# Kube_LoRaWAN_Module.net
KiCad netlist of a schematic drawn in EAGLE
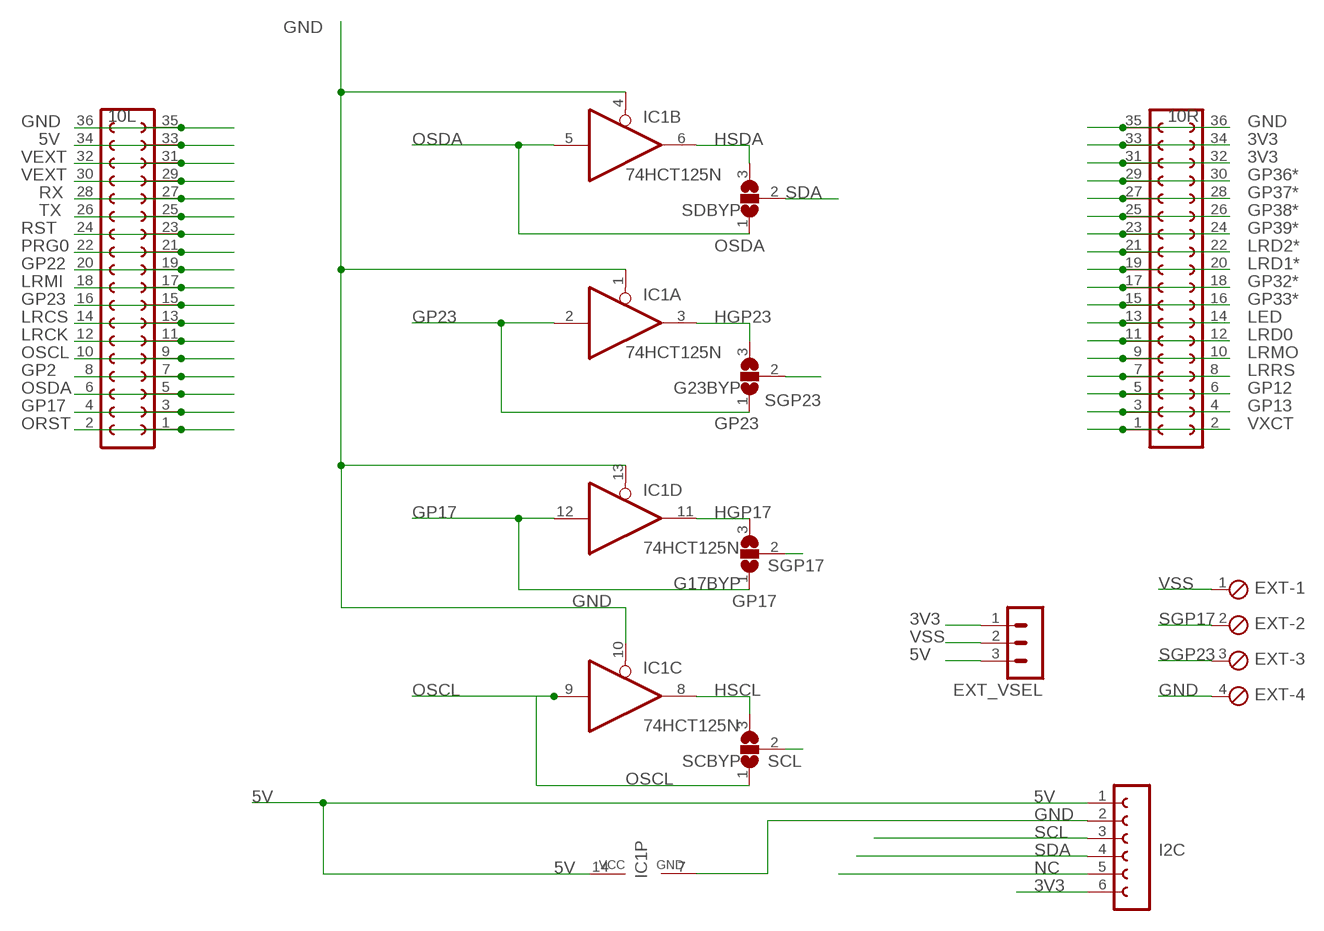
[diagram p0: schematic, sheet 1]

(export (version "E")
  (design (tool "Eeschema 10.0.6"))
  (components
    (comp (ref "10L")
      (value "15")
      (footprint "eagle-import:FE18-2")
      (libsource (lib "eagle-import") (part "FE18-2"))
    )
    (comp (ref "10R")
      (value "15")
      (footprint "eagle-import:FE18-2")
      (libsource (lib "eagle-import") (part "FE18-2"))
    )
    (comp (ref "EXT")
      (value "MPT4")
      (footprint "eagle-import:4POL254")
      (libsource (lib "eagle-import") (part "MPT4"))
    )
    (comp (ref "EXT_VSEL")
      (value "MA03-1")
      (footprint "eagle-import:MA03-1")
      (libsource (lib "eagle-import") (part "MA03-1"))
    )
    (comp (ref "G17BYP")
      (value "SJ2W")
      (footprint "eagle-import:SJ_2")
      (libsource (lib "eagle-import") (part "SJ2W"))
    )
    (comp (ref "G23BYP")
      (value "SJ2W")
      (footprint "eagle-import:SJ_2")
      (libsource (lib "eagle-import") (part "SJ2W"))
    )
    (comp (ref "I2C")
      (value "FE06-1")
      (footprint "eagle-import:FE06")
      (libsource (lib "eagle-import") (part "FE06-1"))
    )
    (comp (ref "IC1")
      (value "74HCT125N")
      (footprint "eagle-import:DIL14")
      (libsource (lib "eagle-import") (part "74125NHCT"))
    )
    (comp (ref "SCBYP")
      (value "SJ2W")
      (footprint "eagle-import:SJ_2")
      (libsource (lib "eagle-import") (part "SJ2W"))
    )
    (comp (ref "SDBYP")
      (value "SJ2W")
      (footprint "eagle-import:SJ_2")
      (libsource (lib "eagle-import") (part "SJ2W"))
    )
  )
  (nets
    (net (code "1") (name "/3V3") (class "Default")
      (node (ref "10R") (pin "31") (pinfunction "31_31") (pintype "passive"))
      (node (ref "10R") (pin "32") (pinfunction "32_32") (pintype "passive"))
      (node (ref "10R") (pin "33") (pinfunction "33_33") (pintype "passive"))
      (node (ref "10R") (pin "34") (pinfunction "34_34") (pintype "passive"))
      (node (ref "EXT_VSEL") (pin "1") (pinfunction "1_1") (pintype "passive"))
      (node (ref "I2C") (pin "6") (pinfunction "6_6") (pintype "passive"))
    )
    (net (code "2") (name "/5V") (class "Default")
      (node (ref "10L") (pin "33") (pinfunction "33_33") (pintype "passive"))
      (node (ref "10L") (pin "34") (pinfunction "34_34") (pintype "passive"))
      (node (ref "EXT_VSEL") (pin "3") (pinfunction "3_3") (pintype "passive"))
      (node (ref "I2C") (pin "1") (pinfunction "1_1") (pintype "passive"))
      (node (ref "IC1") (pin "14") (pinfunction "VCC_14") (pintype "power_in"))
    )
    (net (code "3") (name "/GND") (class "Default")
      (node (ref "10L") (pin "35") (pinfunction "35_35") (pintype "passive"))
      (node (ref "10L") (pin "36") (pinfunction "36_36") (pintype "passive"))
      (node (ref "10R") (pin "35") (pinfunction "35_35") (pintype "passive"))
      (node (ref "10R") (pin "36") (pinfunction "36_36") (pintype "passive"))
      (node (ref "EXT") (pin "4") (pinfunction "1_4") (pintype "passive"))
      (node (ref "I2C") (pin "2") (pinfunction "2_2") (pintype "passive"))
      (node (ref "IC1") (pin "1") (pinfunction "OE_1") (pintype "input"))
      (node (ref "IC1") (pin "10") (pinfunction "OE_10") (pintype "input"))
      (node (ref "IC1") (pin "13") (pinfunction "OE_13") (pintype "input"))
      (node (ref "IC1") (pin "4") (pinfunction "OE_4") (pintype "input"))
      (node (ref "IC1") (pin "7") (pinfunction "GND_7") (pintype "power_in"))
    )
    (net (code "4") (name "/GP2") (class "Default")
      (node (ref "10L") (pin "7") (pinfunction "7_7") (pintype "passive"))
      (node (ref "10L") (pin "8") (pinfunction "8_8") (pintype "passive"))
    )
    (net (code "5") (name "/GP12") (class "Default")
      (node (ref "10R") (pin "5") (pinfunction "5_5") (pintype "passive"))
      (node (ref "10R") (pin "6") (pinfunction "6_6") (pintype "passive"))
    )
    (net (code "6") (name "/GP13") (class "Default")
      (node (ref "10R") (pin "3") (pinfunction "3_3") (pintype "passive"))
      (node (ref "10R") (pin "4") (pinfunction "4_4") (pintype "passive"))
    )
    (net (code "7") (name "/GP17") (class "Default")
      (node (ref "10L") (pin "3") (pinfunction "3_3") (pintype "passive"))
      (node (ref "10L") (pin "4") (pinfunction "4_4") (pintype "passive"))
      (node (ref "G17BYP") (pin "1") (pinfunction "1_1") (pintype "passive"))
      (node (ref "IC1") (pin "12") (pinfunction "I_12") (pintype "input"))
    )
    (net (code "8") (name "/GP22") (class "Default")
      (node (ref "10L") (pin "19") (pinfunction "19_19") (pintype "passive"))
      (node (ref "10L") (pin "20") (pinfunction "20_20") (pintype "passive"))
    )
    (net (code "9") (name "/GP23") (class "Default")
      (node (ref "10L") (pin "15") (pinfunction "15_15") (pintype "passive"))
      (node (ref "10L") (pin "16") (pinfunction "16_16") (pintype "passive"))
      (node (ref "G23BYP") (pin "1") (pinfunction "1_1") (pintype "passive"))
      (node (ref "IC1") (pin "2") (pinfunction "I_2") (pintype "input"))
    )
    (net (code "10") (name "/GP32*") (class "Default")
      (node (ref "10R") (pin "17") (pinfunction "17_17") (pintype "passive"))
      (node (ref "10R") (pin "18") (pinfunction "18_18") (pintype "passive"))
    )
    (net (code "11") (name "/GP33*") (class "Default")
      (node (ref "10R") (pin "15") (pinfunction "15_15") (pintype "passive"))
      (node (ref "10R") (pin "16") (pinfunction "16_16") (pintype "passive"))
    )
    (net (code "12") (name "/GP36*") (class "Default")
      (node (ref "10R") (pin "29") (pinfunction "29_29") (pintype "passive"))
      (node (ref "10R") (pin "30") (pinfunction "30_30") (pintype "passive"))
    )
    (net (code "13") (name "/GP37*") (class "Default")
      (node (ref "10R") (pin "27") (pinfunction "27_27") (pintype "passive"))
      (node (ref "10R") (pin "28") (pinfunction "28_28") (pintype "passive"))
    )
    (net (code "14") (name "/GP38*") (class "Default")
      (node (ref "10R") (pin "25") (pinfunction "25_25") (pintype "passive"))
      (node (ref "10R") (pin "26") (pinfunction "26_26") (pintype "passive"))
    )
    (net (code "15") (name "/GP39*") (class "Default")
      (node (ref "10R") (pin "23") (pinfunction "23_23") (pintype "passive"))
      (node (ref "10R") (pin "24") (pinfunction "24_24") (pintype "passive"))
    )
    (net (code "16") (name "/HGP17") (class "Default")
      (node (ref "G17BYP") (pin "3") (pinfunction "3_3") (pintype "passive"))
      (node (ref "IC1") (pin "11") (pinfunction "O_11") (pintype "tri_state"))
    )
    (net (code "17") (name "/HGP23") (class "Default")
      (node (ref "G23BYP") (pin "3") (pinfunction "3_3") (pintype "passive"))
      (node (ref "IC1") (pin "3") (pinfunction "O_3") (pintype "tri_state"))
    )
    (net (code "18") (name "/HSCL") (class "Default")
      (node (ref "IC1") (pin "8") (pinfunction "O_8") (pintype "tri_state"))
      (node (ref "SCBYP") (pin "3") (pinfunction "3_3") (pintype "passive"))
    )
    (net (code "19") (name "/HSDA") (class "Default")
      (node (ref "IC1") (pin "6") (pinfunction "O_6") (pintype "tri_state"))
      (node (ref "SDBYP") (pin "3") (pinfunction "3_3") (pintype "passive"))
    )
    (net (code "20") (name "/LED") (class "Default")
      (node (ref "10R") (pin "13") (pinfunction "13_13") (pintype "passive"))
      (node (ref "10R") (pin "14") (pinfunction "14_14") (pintype "passive"))
    )
    (net (code "21") (name "/LRCK") (class "Default")
      (node (ref "10L") (pin "11") (pinfunction "11_11") (pintype "passive"))
      (node (ref "10L") (pin "12") (pinfunction "12_12") (pintype "passive"))
    )
    (net (code "22") (name "/LRCS") (class "Default")
      (node (ref "10L") (pin "13") (pinfunction "13_13") (pintype "passive"))
      (node (ref "10L") (pin "14") (pinfunction "14_14") (pintype "passive"))
    )
    (net (code "23") (name "/LRD0") (class "Default")
      (node (ref "10R") (pin "11") (pinfunction "11_11") (pintype "passive"))
      (node (ref "10R") (pin "12") (pinfunction "12_12") (pintype "passive"))
    )
    (net (code "24") (name "/LRD1*") (class "Default")
      (node (ref "10R") (pin "19") (pinfunction "19_19") (pintype "passive"))
      (node (ref "10R") (pin "20") (pinfunction "20_20") (pintype "passive"))
    )
    (net (code "25") (name "/LRD2*") (class "Default")
      (node (ref "10R") (pin "21") (pinfunction "21_21") (pintype "passive"))
      (node (ref "10R") (pin "22") (pinfunction "22_22") (pintype "passive"))
    )
    (net (code "26") (name "/LRMI") (class "Default")
      (node (ref "10L") (pin "17") (pinfunction "17_17") (pintype "passive"))
      (node (ref "10L") (pin "18") (pinfunction "18_18") (pintype "passive"))
    )
    (net (code "27") (name "/LRMO") (class "Default")
      (node (ref "10R") (pin "10") (pinfunction "10_10") (pintype "passive"))
      (node (ref "10R") (pin "9") (pinfunction "9_9") (pintype "passive"))
    )
    (net (code "28") (name "/LRRS") (class "Default")
      (node (ref "10R") (pin "7") (pinfunction "7_7") (pintype "passive"))
      (node (ref "10R") (pin "8") (pinfunction "8_8") (pintype "passive"))
    )
    (net (code "29") (name "/NC") (class "Default")
      (node (ref "I2C") (pin "5") (pinfunction "5_5") (pintype "passive"))
    )
    (net (code "30") (name "/ORST") (class "Default")
      (node (ref "10L") (pin "1") (pinfunction "1_1") (pintype "passive"))
      (node (ref "10L") (pin "2") (pinfunction "2_2") (pintype "passive"))
    )
    (net (code "31") (name "/OSCL") (class "Default")
      (node (ref "10L") (pin "10") (pinfunction "10_10") (pintype "passive"))
      (node (ref "10L") (pin "9") (pinfunction "9_9") (pintype "passive"))
      (node (ref "IC1") (pin "9") (pinfunction "I_9") (pintype "input"))
      (node (ref "SCBYP") (pin "1") (pinfunction "1_1") (pintype "passive"))
    )
    (net (code "32") (name "/OSDA") (class "Default")
      (node (ref "10L") (pin "5") (pinfunction "5_5") (pintype "passive"))
      (node (ref "10L") (pin "6") (pinfunction "6_6") (pintype "passive"))
      (node (ref "IC1") (pin "5") (pinfunction "I_5") (pintype "input"))
      (node (ref "SDBYP") (pin "1") (pinfunction "1_1") (pintype "passive"))
    )
    (net (code "33") (name "/PRG0") (class "Default")
      (node (ref "10L") (pin "21") (pinfunction "21_21") (pintype "passive"))
      (node (ref "10L") (pin "22") (pinfunction "22_22") (pintype "passive"))
    )
    (net (code "34") (name "/RST") (class "Default")
      (node (ref "10L") (pin "23") (pinfunction "23_23") (pintype "passive"))
      (node (ref "10L") (pin "24") (pinfunction "24_24") (pintype "passive"))
    )
    (net (code "35") (name "/RX") (class "Default")
      (node (ref "10L") (pin "27") (pinfunction "27_27") (pintype "passive"))
      (node (ref "10L") (pin "28") (pinfunction "28_28") (pintype "passive"))
    )
    (net (code "36") (name "/SCL") (class "Default")
      (node (ref "I2C") (pin "3") (pinfunction "3_3") (pintype "passive"))
      (node (ref "SCBYP") (pin "2") (pinfunction "2_2") (pintype "passive"))
    )
    (net (code "37") (name "/SDA") (class "Default")
      (node (ref "I2C") (pin "4") (pinfunction "4_4") (pintype "passive"))
      (node (ref "SDBYP") (pin "2") (pinfunction "2_2") (pintype "passive"))
    )
    (net (code "38") (name "/SGP17") (class "Default")
      (node (ref "EXT") (pin "2") (pinfunction "1_2") (pintype "passive"))
      (node (ref "G17BYP") (pin "2") (pinfunction "2_2") (pintype "passive"))
    )
    (net (code "39") (name "/SGP23") (class "Default")
      (node (ref "EXT") (pin "3") (pinfunction "1_3") (pintype "passive"))
      (node (ref "G23BYP") (pin "2") (pinfunction "2_2") (pintype "passive"))
    )
    (net (code "40") (name "/TX") (class "Default")
      (node (ref "10L") (pin "25") (pinfunction "25_25") (pintype "passive"))
      (node (ref "10L") (pin "26") (pinfunction "26_26") (pintype "passive"))
    )
    (net (code "41") (name "/VEXT") (class "Default")
      (node (ref "10L") (pin "29") (pinfunction "29_29") (pintype "passive"))
      (node (ref "10L") (pin "30") (pinfunction "30_30") (pintype "passive"))
      (node (ref "10L") (pin "31") (pinfunction "31_31") (pintype "passive"))
      (node (ref "10L") (pin "32") (pinfunction "32_32") (pintype "passive"))
    )
    (net (code "42") (name "/VSS") (class "Default")
      (node (ref "EXT") (pin "1") (pinfunction "1_1") (pintype "passive"))
      (node (ref "EXT_VSEL") (pin "2") (pinfunction "2_2") (pintype "passive"))
    )
    (net (code "43") (name "/VXCT") (class "Default")
      (node (ref "10R") (pin "1") (pinfunction "1_1") (pintype "passive"))
      (node (ref "10R") (pin "2") (pinfunction "2_2") (pintype "passive"))
    )
  )
)
